# 3923Final.net
KiCad netlist of a schematic drawn in Altium Designer
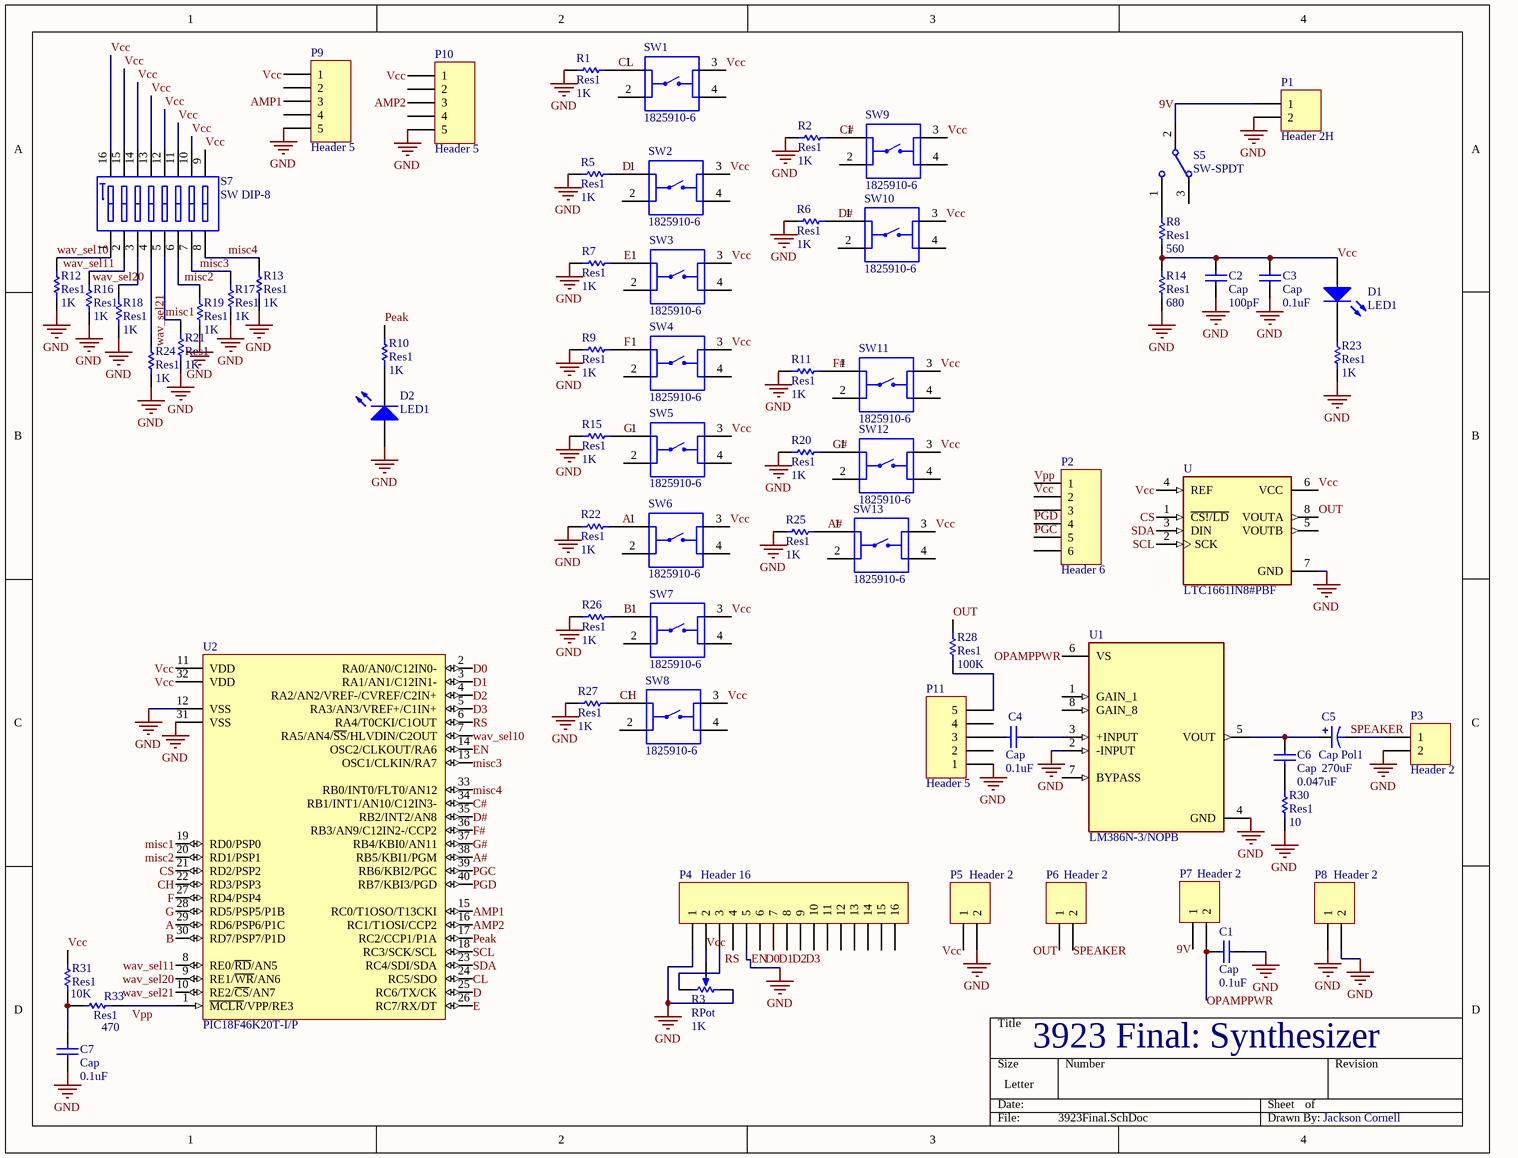
[diagram p0: 3923Final.SchDoc]

(export (version "E")
  (design (tool "Eeschema 10.0.6"))
  (components
    (comp (ref "C1")
      (value "Cap")
      (footprint "RAD-0.3")
      (description "Capacitor")
      (fields (field (name "ALTIUM_VALUE") "0.1uF") (field (name "PUBLISHER") "Altium Limited"))
      (libsource (lib "Miscellaneous Devices") (part "Cap"))
    )
    (comp (ref "C2")
      (value "Cap")
      (footprint "RAD-0.3")
      (description "Capacitor")
      (fields (field (name "ALTIUM_VALUE") "100pF") (field (name "PUBLISHER") "Altium Limited"))
      (libsource (lib "Miscellaneous Devices") (part "Cap"))
    )
    (comp (ref "C3")
      (value "Cap")
      (footprint "RAD-0.3")
      (description "Capacitor")
      (fields (field (name "ALTIUM_VALUE") "0.1uF") (field (name "PUBLISHER") "Altium Limited"))
      (libsource (lib "Miscellaneous Devices") (part "Cap"))
    )
    (comp (ref "C4")
      (value "Cap")
      (footprint "RAD-0.3")
      (description "Capacitor")
      (fields (field (name "ALTIUM_VALUE") "0.1uF") (field (name "PUBLISHER") "Altium Limited"))
      (libsource (lib "Miscellaneous Devices") (part "Cap"))
    )
    (comp (ref "C5")
      (value "Cap Pol1")
      (footprint "RB7.6-15")
      (description "Polarized Capacitor (Radial)")
      (fields (field (name "ALTIUM_VALUE") "270uF") (field (name "PUBLISHER") "Altium Limited"))
      (libsource (lib "Miscellaneous Devices") (part "Cap Pol1"))
    )
    (comp (ref "C6")
      (value "Cap")
      (footprint "RAD-0.3")
      (description "Capacitor")
      (fields (field (name "ALTIUM_VALUE") "0.047uF") (field (name "PUBLISHER") "Altium Limited"))
      (libsource (lib "Miscellaneous Devices") (part "Cap"))
    )
    (comp (ref "C7")
      (value "Cap")
      (footprint "RAD-0.3")
      (description "Capacitor")
      (fields (field (name "ALTIUM_VALUE") "0.1uF") (field (name "PUBLISHER") "Altium Limited"))
      (libsource (lib "Miscellaneous Devices") (part "Cap"))
    )
    (comp (ref "D1")
      (value "LED1")
      (footprint "LED-1")
      (description "Typical RED GaAs LED")
      (fields (field (name "PUBLISHER") "Altium Limited"))
      (libsource (lib "Miscellaneous Devices") (part "LED1"))
    )
    (comp (ref "D2")
      (value "LED1")
      (footprint "LED-1")
      (description "Typical RED GaAs LED")
      (fields (field (name "PUBLISHER") "Altium Limited"))
      (libsource (lib "Miscellaneous Devices") (part "LED1"))
    )
    (comp (ref "P1")
      (value "Header 2H")
      (footprint "HDR1X2H")
      (description "Header, 2-Pin, Right Angle")
      (fields (field (name "PUBLISHER") "Altium Limited"))
      (libsource (lib "Miscellaneous Connectors") (part "Header 2H"))
    )
    (comp (ref "P2")
      (value "Header 6")
      (footprint "HDR1X6")
      (description "Header, 6-Pin")
      (fields (field (name "PUBLISHER") "Altium Limited"))
      (libsource (lib "Miscellaneous Connectors") (part "Header 6"))
    )
    (comp (ref "P3")
      (value "Header 2")
      (footprint "HDR1X2")
      (description "Header, 2-Pin")
      (fields (field (name "PUBLISHER") "Altium Limited"))
      (libsource (lib "") (part "Header 2_1"))
    )
    (comp (ref "P4")
      (value "Header 16")
      (footprint "HDR1X16")
      (description "Header, 16-Pin")
      (fields (field (name "PUBLISHER") "Altium Limited"))
      (libsource (lib "Miscellaneous Connectors") (part "Header 16"))
    )
    (comp (ref "P5")
      (value "Header 2")
      (footprint "HDR1X2")
      (description "Header, 2-Pin")
      (fields (field (name "PUBLISHER") "Altium Limited"))
      (libsource (lib "Miscellaneous Connectors") (part "Header 2"))
    )
    (comp (ref "P6")
      (value "Header 2")
      (footprint "HDR1X2")
      (description "Header, 2-Pin")
      (fields (field (name "PUBLISHER") "Altium Limited"))
      (libsource (lib "Miscellaneous Connectors") (part "Header 2"))
    )
    (comp (ref "P7")
      (value "Header 2")
      (footprint "HDR1X2")
      (description "Header, 2-Pin")
      (fields (field (name "PUBLISHER") "Altium Limited"))
      (libsource (lib "Miscellaneous Connectors") (part "Header 2"))
    )
    (comp (ref "P8")
      (value "Header 2")
      (footprint "HDR1X2")
      (description "Header, 2-Pin")
      (fields (field (name "PUBLISHER") "Altium Limited"))
      (libsource (lib "Miscellaneous Connectors") (part "Header 2"))
    )
    (comp (ref "P9")
      (value "Header 5")
      (footprint "HDR1X5")
      (description "Header, 5-Pin")
      (fields (field (name "PUBLISHER") "Altium Limited"))
      (libsource (lib "") (part "Header 5_1"))
    )
    (comp (ref "P10")
      (value "Header 5")
      (footprint "HDR1X5")
      (description "Header, 5-Pin")
      (fields (field (name "PUBLISHER") "Altium Limited"))
      (libsource (lib "") (part "Header 5_1"))
    )
    (comp (ref "P11")
      (value "Header 5")
      (footprint "HDR1X5")
      (description "Header, 5-Pin")
      (fields (field (name "PUBLISHER") "Altium Limited"))
      (libsource (lib "Miscellaneous Connectors") (part "Header 5"))
    )
    (comp (ref "R1")
      (value "Res1")
      (footprint "AXIAL-0.3")
      (description "Resistor")
      (fields (field (name "ALTIUM_VALUE") "1K") (field (name "PUBLISHER") "Altium Limited"))
      (libsource (lib "Miscellaneous Devices") (part "Res1"))
    )
    (comp (ref "R2")
      (value "Res1")
      (footprint "AXIAL-0.3")
      (description "Resistor")
      (fields (field (name "ALTIUM_VALUE") "1K") (field (name "PUBLISHER") "Altium Limited"))
      (libsource (lib "Miscellaneous Devices") (part "Res1"))
    )
    (comp (ref "R3")
      (value "RPot")
      (footprint "VR5")
      (description "Potentiometer")
      (fields (field (name "ALTIUM_VALUE") "1K") (field (name "PUBLISHER") "Altium Limited"))
      (libsource (lib "Miscellaneous Devices") (part "RPot"))
    )
    (comp (ref "R5")
      (value "Res1")
      (footprint "AXIAL-0.3")
      (description "Resistor")
      (fields (field (name "ALTIUM_VALUE") "1K") (field (name "PUBLISHER") "Altium Limited"))
      (libsource (lib "Miscellaneous Devices") (part "Res1"))
    )
    (comp (ref "R6")
      (value "Res1")
      (footprint "AXIAL-0.3")
      (description "Resistor")
      (fields (field (name "ALTIUM_VALUE") "1K") (field (name "PUBLISHER") "Altium Limited"))
      (libsource (lib "Miscellaneous Devices") (part "Res1"))
    )
    (comp (ref "R7")
      (value "Res1")
      (footprint "AXIAL-0.3")
      (description "Resistor")
      (fields (field (name "ALTIUM_VALUE") "1K") (field (name "PUBLISHER") "Altium Limited"))
      (libsource (lib "Miscellaneous Devices") (part "Res1"))
    )
    (comp (ref "R8")
      (value "Res1")
      (footprint "AXIAL-0.3")
      (description "Resistor")
      (fields (field (name "ALTIUM_VALUE") "560") (field (name "PUBLISHER") "Altium Limited"))
      (libsource (lib "Miscellaneous Devices") (part "Res1"))
    )
    (comp (ref "R9")
      (value "Res1")
      (footprint "AXIAL-0.3")
      (description "Resistor")
      (fields (field (name "ALTIUM_VALUE") "1K") (field (name "PUBLISHER") "Altium Limited"))
      (libsource (lib "Miscellaneous Devices") (part "Res1"))
    )
    (comp (ref "R10")
      (value "Res1")
      (footprint "AXIAL-0.3")
      (description "Resistor")
      (fields (field (name "ALTIUM_VALUE") "1K") (field (name "PUBLISHER") "Altium Limited"))
      (libsource (lib "Miscellaneous Devices") (part "Res1"))
    )
    (comp (ref "R11")
      (value "Res1")
      (footprint "AXIAL-0.3")
      (description "Resistor")
      (fields (field (name "ALTIUM_VALUE") "1K") (field (name "PUBLISHER") "Altium Limited"))
      (libsource (lib "Miscellaneous Devices") (part "Res1"))
    )
    (comp (ref "R12")
      (value "Res1")
      (footprint "AXIAL-0.3")
      (description "Resistor")
      (fields (field (name "ALTIUM_VALUE") "1K") (field (name "PUBLISHER") "Altium Limited"))
      (libsource (lib "Miscellaneous Devices") (part "Res1"))
    )
    (comp (ref "R13")
      (value "Res1")
      (footprint "AXIAL-0.3")
      (description "Resistor")
      (fields (field (name "ALTIUM_VALUE") "1K") (field (name "PUBLISHER") "Altium Limited"))
      (libsource (lib "Miscellaneous Devices") (part "Res1"))
    )
    (comp (ref "R14")
      (value "Res1")
      (footprint "AXIAL-0.3")
      (description "Resistor")
      (fields (field (name "ALTIUM_VALUE") "680") (field (name "PUBLISHER") "Altium Limited"))
      (libsource (lib "Miscellaneous Devices") (part "Res1"))
    )
    (comp (ref "R15")
      (value "Res1")
      (footprint "AXIAL-0.3")
      (description "Resistor")
      (fields (field (name "ALTIUM_VALUE") "1K") (field (name "PUBLISHER") "Altium Limited"))
      (libsource (lib "Miscellaneous Devices") (part "Res1"))
    )
    (comp (ref "R16")
      (value "Res1")
      (footprint "AXIAL-0.3")
      (description "Resistor")
      (fields (field (name "ALTIUM_VALUE") "1K") (field (name "PUBLISHER") "Altium Limited"))
      (libsource (lib "Miscellaneous Devices") (part "Res1"))
    )
    (comp (ref "R17")
      (value "Res1")
      (footprint "AXIAL-0.3")
      (description "Resistor")
      (fields (field (name "ALTIUM_VALUE") "1K") (field (name "PUBLISHER") "Altium Limited"))
      (libsource (lib "Miscellaneous Devices") (part "Res1"))
    )
    (comp (ref "R18")
      (value "Res1")
      (footprint "AXIAL-0.3")
      (description "Resistor")
      (fields (field (name "ALTIUM_VALUE") "1K") (field (name "PUBLISHER") "Altium Limited"))
      (libsource (lib "Miscellaneous Devices") (part "Res1"))
    )
    (comp (ref "R19")
      (value "Res1")
      (footprint "AXIAL-0.3")
      (description "Resistor")
      (fields (field (name "ALTIUM_VALUE") "1K") (field (name "PUBLISHER") "Altium Limited"))
      (libsource (lib "Miscellaneous Devices") (part "Res1"))
    )
    (comp (ref "R20")
      (value "Res1")
      (footprint "AXIAL-0.3")
      (description "Resistor")
      (fields (field (name "ALTIUM_VALUE") "1K") (field (name "PUBLISHER") "Altium Limited"))
      (libsource (lib "Miscellaneous Devices") (part "Res1"))
    )
    (comp (ref "R21")
      (value "Res1")
      (footprint "AXIAL-0.3")
      (description "Resistor")
      (fields (field (name "ALTIUM_VALUE") "1K") (field (name "PUBLISHER") "Altium Limited"))
      (libsource (lib "Miscellaneous Devices") (part "Res1"))
    )
    (comp (ref "R22")
      (value "Res1")
      (footprint "AXIAL-0.3")
      (description "Resistor")
      (fields (field (name "ALTIUM_VALUE") "1K") (field (name "PUBLISHER") "Altium Limited"))
      (libsource (lib "Miscellaneous Devices") (part "Res1"))
    )
    (comp (ref "R23")
      (value "Res1")
      (footprint "AXIAL-0.3")
      (description "Resistor")
      (fields (field (name "ALTIUM_VALUE") "1K") (field (name "PUBLISHER") "Altium Limited"))
      (libsource (lib "Miscellaneous Devices") (part "Res1"))
    )
    (comp (ref "R24")
      (value "Res1")
      (footprint "AXIAL-0.3")
      (description "Resistor")
      (fields (field (name "ALTIUM_VALUE") "1K") (field (name "PUBLISHER") "Altium Limited"))
      (libsource (lib "Miscellaneous Devices") (part "Res1"))
    )
    (comp (ref "R25")
      (value "Res1")
      (footprint "AXIAL-0.3")
      (description "Resistor")
      (fields (field (name "ALTIUM_VALUE") "1K") (field (name "PUBLISHER") "Altium Limited"))
      (libsource (lib "Miscellaneous Devices") (part "Res1"))
    )
    (comp (ref "R26")
      (value "Res1")
      (footprint "AXIAL-0.3")
      (description "Resistor")
      (fields (field (name "ALTIUM_VALUE") "1K") (field (name "PUBLISHER") "Altium Limited"))
      (libsource (lib "Miscellaneous Devices") (part "Res1"))
    )
    (comp (ref "R27")
      (value "Res1")
      (footprint "AXIAL-0.3")
      (description "Resistor")
      (fields (field (name "ALTIUM_VALUE") "1K") (field (name "PUBLISHER") "Altium Limited"))
      (libsource (lib "Miscellaneous Devices") (part "Res1"))
    )
    (comp (ref "R28")
      (value "Res1")
      (footprint "AXIAL-0.3")
      (description "Resistor")
      (fields (field (name "ALTIUM_VALUE") "100K") (field (name "PUBLISHER") "Altium Limited"))
      (libsource (lib "Miscellaneous Devices") (part "Res1"))
    )
    (comp (ref "R30")
      (value "Res1")
      (footprint "AXIAL-0.3")
      (description "Resistor")
      (fields (field (name "ALTIUM_VALUE") "10") (field (name "PUBLISHER") "Altium Limited"))
      (libsource (lib "Miscellaneous Devices") (part "Res1"))
    )
    (comp (ref "R31")
      (value "Res1")
      (footprint "AXIAL-0.3")
      (description "Resistor")
      (fields (field (name "ALTIUM_VALUE") "10K") (field (name "PUBLISHER") "Altium Limited"))
      (libsource (lib "Miscellaneous Devices") (part "Res1"))
    )
    (comp (ref "R33")
      (value "Res1")
      (footprint "AXIAL-0.3")
      (description "Resistor")
      (fields (field (name "ALTIUM_VALUE") "470") (field (name "PUBLISHER") "Altium Limited"))
      (libsource (lib "Miscellaneous Devices") (part "Res1"))
    )
    (comp (ref "S5")
      (value "SW-SPDT")
      (footprint "TL36WW15050")
      (description "SPDT Subminiature Toggle Switch, Right Angle Mounting, Vertical Actuation")
      (fields (field (name "PUBLISHER") "Altium Limited"))
      (libsource (lib "Miscellaneous Devices") (part "SW-SPDT"))
    )
    (comp (ref "S7")
      (value "SW DIP-8")
      (footprint "DIP-16")
      (description "DIP Switch, 8 Position, SPST")
      (fields (field (name "PUBLISHER") "Altium Limited"))
      (libsource (lib "Miscellaneous Devices") (part "SW DIP-8"))
    )
    (comp (ref "SW1")
      (value "1825910-6")
      (footprint "SW_1825910-6-4")
      (description "Switch Push Button OFF _ON_ SPST Round Button 0.05A 24VDC Momentary Contact PC Pins Thru-Hole")
      (fields (field (name "MF") "TE Connectivity") (field (name "DIGI-KEY_PART_NUMBER") "450-1650-ND"))
      (libsource (lib "1825910-6") (part "1825910-6"))
    )
    (comp (ref "SW2")
      (value "1825910-6")
      (footprint "SW_1825910-6-4")
      (description "Switch Push Button OFF _ON_ SPST Round Button 0.05A 24VDC Momentary Contact PC Pins Thru-Hole")
      (fields (field (name "MF") "TE Connectivity") (field (name "DIGI-KEY_PART_NUMBER") "450-1650-ND"))
      (libsource (lib "1825910-6") (part "1825910-6"))
    )
    (comp (ref "SW3")
      (value "1825910-6")
      (footprint "SW_1825910-6-4")
      (description "Switch Push Button OFF _ON_ SPST Round Button 0.05A 24VDC Momentary Contact PC Pins Thru-Hole")
      (fields (field (name "MF") "TE Connectivity") (field (name "DIGI-KEY_PART_NUMBER") "450-1650-ND"))
      (libsource (lib "1825910-6") (part "1825910-6"))
    )
    (comp (ref "SW4")
      (value "1825910-6")
      (footprint "SW_1825910-6-4")
      (description "Switch Push Button OFF _ON_ SPST Round Button 0.05A 24VDC Momentary Contact PC Pins Thru-Hole")
      (fields (field (name "MF") "TE Connectivity") (field (name "DIGI-KEY_PART_NUMBER") "450-1650-ND"))
      (libsource (lib "1825910-6") (part "1825910-6"))
    )
    (comp (ref "SW5")
      (value "1825910-6")
      (footprint "SW_1825910-6-4")
      (description "Switch Push Button OFF _ON_ SPST Round Button 0.05A 24VDC Momentary Contact PC Pins Thru-Hole")
      (fields (field (name "MF") "TE Connectivity") (field (name "DIGI-KEY_PART_NUMBER") "450-1650-ND"))
      (libsource (lib "1825910-6") (part "1825910-6"))
    )
    (comp (ref "SW6")
      (value "1825910-6")
      (footprint "SW_1825910-6-4")
      (description "Switch Push Button OFF _ON_ SPST Round Button 0.05A 24VDC Momentary Contact PC Pins Thru-Hole")
      (fields (field (name "MF") "TE Connectivity") (field (name "DIGI-KEY_PART_NUMBER") "450-1650-ND"))
      (libsource (lib "1825910-6") (part "1825910-6"))
    )
    (comp (ref "SW7")
      (value "1825910-6")
      (footprint "SW_1825910-6-4")
      (description "Switch Push Button OFF _ON_ SPST Round Button 0.05A 24VDC Momentary Contact PC Pins Thru-Hole")
      (fields (field (name "MF") "TE Connectivity") (field (name "DIGI-KEY_PART_NUMBER") "450-1650-ND"))
      (libsource (lib "1825910-6") (part "1825910-6"))
    )
    (comp (ref "SW8")
      (value "1825910-6")
      (footprint "SW_1825910-6-4")
      (description "Switch Push Button OFF _ON_ SPST Round Button 0.05A 24VDC Momentary Contact PC Pins Thru-Hole")
      (fields (field (name "MF") "TE Connectivity") (field (name "DIGI-KEY_PART_NUMBER") "450-1650-ND"))
      (libsource (lib "1825910-6") (part "1825910-6"))
    )
    (comp (ref "SW9")
      (value "1825910-6")
      (footprint "SW_1825910-6-4")
      (description "Switch Push Button OFF _ON_ SPST Round Button 0.05A 24VDC Momentary Contact PC Pins Thru-Hole")
      (fields (field (name "MF") "TE Connectivity") (field (name "DIGI-KEY_PART_NUMBER") "450-1650-ND"))
      (libsource (lib "1825910-6") (part "1825910-6"))
    )
    (comp (ref "SW10")
      (value "1825910-6")
      (footprint "SW_1825910-6-4")
      (description "Switch Push Button OFF _ON_ SPST Round Button 0.05A 24VDC Momentary Contact PC Pins Thru-Hole")
      (fields (field (name "MF") "TE Connectivity") (field (name "DIGI-KEY_PART_NUMBER") "450-1650-ND"))
      (libsource (lib "1825910-6") (part "1825910-6"))
    )
    (comp (ref "SW11")
      (value "1825910-6")
      (footprint "SW_1825910-6-4")
      (description "Switch Push Button OFF _ON_ SPST Round Button 0.05A 24VDC Momentary Contact PC Pins Thru-Hole")
      (fields (field (name "MF") "TE Connectivity") (field (name "DIGI-KEY_PART_NUMBER") "450-1650-ND"))
      (libsource (lib "1825910-6") (part "1825910-6"))
    )
    (comp (ref "SW12")
      (value "1825910-6")
      (footprint "SW_1825910-6-4")
      (description "Switch Push Button OFF _ON_ SPST Round Button 0.05A 24VDC Momentary Contact PC Pins Thru-Hole")
      (fields (field (name "MF") "TE Connectivity") (field (name "DIGI-KEY_PART_NUMBER") "450-1650-ND"))
      (libsource (lib "1825910-6") (part "1825910-6"))
    )
    (comp (ref "SW13")
      (value "1825910-6")
      (footprint "SW_1825910-6-4")
      (description "Switch Push Button OFF _ON_ SPST Round Button 0.05A 24VDC Momentary Contact PC Pins Thru-Hole")
      (fields (field (name "MF") "TE Connectivity") (field (name "DIGI-KEY_PART_NUMBER") "450-1650-ND"))
      (libsource (lib "1825910-6") (part "1825910-6"))
    )
    (comp (ref "U")
      (value "LTC1661IN8#PBF")
      (footprint "DIP794W45P254L959H508Q8")
      (description "10 Bit Digital to Analog Converter 2 8-PDIP")
      (fields (field (name "MF") "Linear Technology/Analog Devices"))
      (libsource (lib "LTC1661IN8_PBF") (part "LTC1661IN8#PBF"))
    )
    (comp (ref "U1")
      (value "LM386N-3/NOPB")
      (footprint "DIP794W45P254L959H508Q8")
      (libsource (lib "LM386N-3_NOPB") (part "LM386N-3/NOPB"))
    )
    (comp (ref "U2")
      (value "PIC18F46K20T-I/P")
      (footprint "PDIP600-P40")
      (libsource (lib "Microchip PIC18") (part "PIC18F46K20T-I/P"))
    )
  )
  (nets
    (net (code "1") (name "/9V") (class "Default")
      (node (ref "P1") (pin "1") (pinfunction "1_1") (pintype "passive"))
      (node (ref "P7") (pin "1") (pinfunction "1_1") (pintype "passive"))
      (node (ref "S5") (pin "2") (pinfunction "2_2") (pintype "passive"))
    )
    (net (code "2") (name "/A") (class "Default")
      (node (ref "R22") (pin "1") (pinfunction "1_1") (pintype "passive"))
      (node (ref "SW6") (pin "1") (pinfunction "1_1") (pintype "passive"))
      (node (ref "U2") (pin "29") (pinfunction "RD6/PSP6/P1C_29") (pintype "bidirectional"))
    )
    (net (code "3") (name "/A#") (class "Default")
      (node (ref "R25") (pin "1") (pinfunction "1_1") (pintype "passive"))
      (node (ref "SW13") (pin "1") (pinfunction "1_1") (pintype "passive"))
      (node (ref "U2") (pin "38") (pinfunction "RB5/KBI1/PGM_38") (pintype "bidirectional"))
    )
    (net (code "4") (name "/AMP1") (class "Default")
      (node (ref "P9") (pin "3") (pinfunction "3_3") (pintype "passive"))
      (node (ref "U2") (pin "15") (pinfunction "RC0/T1OSO/T13CKI_15") (pintype "bidirectional"))
    )
    (net (code "5") (name "/AMP2") (class "Default")
      (node (ref "P10") (pin "3") (pinfunction "3_3") (pintype "passive"))
      (node (ref "U2") (pin "16") (pinfunction "RC1/T1OSI/CCP2_16") (pintype "bidirectional"))
    )
    (net (code "6") (name "/B") (class "Default")
      (node (ref "R26") (pin "1") (pinfunction "1_1") (pintype "passive"))
      (node (ref "SW7") (pin "1") (pinfunction "1_1") (pintype "passive"))
      (node (ref "U2") (pin "30") (pinfunction "RD7/PSP7/P1D_30") (pintype "bidirectional"))
    )
    (net (code "7") (name "/C#") (class "Default")
      (node (ref "R2") (pin "1") (pinfunction "1_1") (pintype "passive"))
      (node (ref "SW9") (pin "1") (pinfunction "1_1") (pintype "passive"))
      (node (ref "U2") (pin "34") (pinfunction "RB1/INT1/AN10/C12IN3-_34") (pintype "bidirectional"))
    )
    (net (code "8") (name "/CH") (class "Default")
      (node (ref "R27") (pin "1") (pinfunction "1_1") (pintype "passive"))
      (node (ref "SW8") (pin "1") (pinfunction "1_1") (pintype "passive"))
      (node (ref "U2") (pin "22") (pinfunction "RD3/PSP3_22") (pintype "bidirectional"))
    )
    (net (code "9") (name "/CL") (class "Default")
      (node (ref "R1") (pin "2") (pinfunction "2_2") (pintype "passive"))
      (node (ref "SW1") (pin "1") (pinfunction "1_1") (pintype "passive"))
      (node (ref "U2") (pin "24") (pinfunction "RC5/SDO_24") (pintype "bidirectional"))
    )
    (net (code "10") (name "/CS") (class "Default")
      (node (ref "U") (pin "1") (pinfunction "~{CS!/LD}_1") (pintype "input"))
      (node (ref "U2") (pin "21") (pinfunction "RD2/PSP2_21") (pintype "bidirectional"))
    )
    (net (code "11") (name "/D") (class "Default")
      (node (ref "R5") (pin "1") (pinfunction "1_1") (pintype "passive"))
      (node (ref "SW2") (pin "1") (pinfunction "1_1") (pintype "passive"))
      (node (ref "U2") (pin "25") (pinfunction "RC6/TX/CK_25") (pintype "bidirectional"))
    )
    (net (code "12") (name "/D#") (class "Default")
      (node (ref "R6") (pin "1") (pinfunction "1_1") (pintype "passive"))
      (node (ref "SW10") (pin "1") (pinfunction "1_1") (pintype "passive"))
      (node (ref "U2") (pin "35") (pinfunction "RB2/INT2/AN8_35") (pintype "bidirectional"))
    )
    (net (code "13") (name "/D0") (class "Default")
      (node (ref "P4") (pin "7") (pinfunction "7_7") (pintype "passive"))
      (node (ref "U2") (pin "2") (pinfunction "RA0/AN0/C12IN0-_2") (pintype "bidirectional"))
    )
    (net (code "14") (name "/D1") (class "Default")
      (node (ref "P4") (pin "8") (pinfunction "8_8") (pintype "passive"))
      (node (ref "U2") (pin "3") (pinfunction "RA1/AN1/C12IN1-_3") (pintype "bidirectional"))
    )
    (net (code "15") (name "/D2") (class "Default")
      (node (ref "P4") (pin "9") (pinfunction "9_9") (pintype "passive"))
      (node (ref "U2") (pin "4") (pinfunction "RA2/AN2/VREF-/CVREF/C2IN+_4") (pintype "bidirectional"))
    )
    (net (code "16") (name "/D3") (class "Default")
      (node (ref "P4") (pin "10") (pinfunction "10_10") (pintype "passive"))
      (node (ref "U2") (pin "5") (pinfunction "RA3/AN3/VREF+/C1IN+_5") (pintype "bidirectional"))
    )
    (net (code "17") (name "/E") (class "Default")
      (node (ref "R7") (pin "1") (pinfunction "1_1") (pintype "passive"))
      (node (ref "SW3") (pin "1") (pinfunction "1_1") (pintype "passive"))
      (node (ref "U2") (pin "26") (pinfunction "RC7/RX/DT_26") (pintype "bidirectional"))
    )
    (net (code "18") (name "/EN") (class "Default")
      (node (ref "P4") (pin "6") (pinfunction "6_6") (pintype "passive"))
      (node (ref "U2") (pin "14") (pinfunction "OSC2/CLKOUT/RA6_14") (pintype "bidirectional"))
    )
    (net (code "19") (name "/F") (class "Default")
      (node (ref "R9") (pin "1") (pinfunction "1_1") (pintype "passive"))
      (node (ref "SW4") (pin "1") (pinfunction "1_1") (pintype "passive"))
      (node (ref "U2") (pin "27") (pinfunction "RD4/PSP4_27") (pintype "bidirectional"))
    )
    (net (code "20") (name "/F#") (class "Default")
      (node (ref "R11") (pin "1") (pinfunction "1_1") (pintype "passive"))
      (node (ref "SW11") (pin "1") (pinfunction "1_1") (pintype "passive"))
      (node (ref "U2") (pin "36") (pinfunction "RB3/AN9/C12IN2-/CCP2_36") (pintype "bidirectional"))
    )
    (net (code "21") (name "/G") (class "Default")
      (node (ref "R15") (pin "1") (pinfunction "1_1") (pintype "passive"))
      (node (ref "SW5") (pin "1") (pinfunction "1_1") (pintype "passive"))
      (node (ref "U2") (pin "28") (pinfunction "RD5/PSP5/P1B_28") (pintype "bidirectional"))
    )
    (net (code "22") (name "/G#") (class "Default")
      (node (ref "R20") (pin "1") (pinfunction "1_1") (pintype "passive"))
      (node (ref "SW12") (pin "1") (pinfunction "1_1") (pintype "passive"))
      (node (ref "U2") (pin "37") (pinfunction "RB4/KBI0/AN11_37") (pintype "bidirectional"))
    )
    (net (code "23") (name "/OPAMPPWR") (class "Default")
      (node (ref "C1") (pin "2") (pinfunction "2_2") (pintype "passive"))
      (node (ref "P7") (pin "2") (pinfunction "2_2") (pintype "passive"))
      (node (ref "U1") (pin "6") (pinfunction "VS_6") (pintype "power_in"))
    )
    (net (code "24") (name "/OUT") (class "Default")
      (node (ref "P6") (pin "1") (pinfunction "1_1") (pintype "passive"))
      (node (ref "R28") (pin "2") (pinfunction "2_2") (pintype "passive"))
      (node (ref "U") (pin "8") (pinfunction "VOUTA_8") (pintype "output"))
    )
    (net (code "25") (name "/PGC") (class "Default")
      (node (ref "P2") (pin "5") (pinfunction "5_5") (pintype "passive"))
      (node (ref "U2") (pin "39") (pinfunction "RB6/KBI2/PGC_39") (pintype "bidirectional"))
    )
    (net (code "26") (name "/PGD") (class "Default")
      (node (ref "P2") (pin "4") (pinfunction "4_4") (pintype "passive"))
      (node (ref "U2") (pin "40") (pinfunction "RB7/KBI3/PGD_40") (pintype "bidirectional"))
    )
    (net (code "27") (name "/Peak") (class "Default")
      (node (ref "R10") (pin "1") (pinfunction "1_1") (pintype "passive"))
      (node (ref "U2") (pin "17") (pinfunction "RC2/CCP1/P1A_17") (pintype "bidirectional"))
    )
    (net (code "28") (name "/RS") (class "Default")
      (node (ref "P4") (pin "4") (pinfunction "4_4") (pintype "passive"))
      (node (ref "U2") (pin "6") (pinfunction "RA4/T0CKI/C1OUT_6") (pintype "bidirectional"))
    )
    (net (code "29") (name "/SCL") (class "Default")
      (node (ref "U") (pin "2") (pinfunction "SCK_2") (pintype "input"))
      (node (ref "U2") (pin "18") (pinfunction "RC3/SCK/SCL_18") (pintype "bidirectional"))
    )
    (net (code "30") (name "/SDA") (class "Default")
      (node (ref "U") (pin "3") (pinfunction "DIN_3") (pintype "input"))
      (node (ref "U2") (pin "23") (pinfunction "RC4/SDI/SDA_23") (pintype "bidirectional"))
    )
    (net (code "31") (name "/SPEAKER") (class "Default")
      (node (ref "C5") (pin "2") (pinfunction "2_2") (pintype "passive"))
      (node (ref "P3") (pin "1") (pinfunction "1_1") (pintype "passive"))
      (node (ref "P6") (pin "2") (pinfunction "2_2") (pintype "passive"))
    )
    (net (code "32") (name "/Vcc") (class "Default")
      (node (ref "C2") (pin "2") (pinfunction "2_2") (pintype "passive"))
      (node (ref "C3") (pin "2") (pinfunction "2_2") (pintype "passive"))
      (node (ref "D1") (pin "1") (pinfunction "A_1") (pintype "passive"))
      (node (ref "P10") (pin "1") (pinfunction "1_1") (pintype "passive"))
      (node (ref "P2") (pin "2") (pinfunction "2_2") (pintype "passive"))
      (node (ref "P4") (pin "2") (pinfunction "2_2") (pintype "passive"))
      (node (ref "P5") (pin "1") (pinfunction "1_1") (pintype "passive"))
      (node (ref "P9") (pin "1") (pinfunction "1_1") (pintype "passive"))
      (node (ref "R14") (pin "2") (pinfunction "2_2") (pintype "passive"))
      (node (ref "R3") (pin "3") (pinfunction "TAP_3") (pintype "passive"))
      (node (ref "R31") (pin "2") (pinfunction "2_2") (pintype "passive"))
      (node (ref "R8") (pin "1") (pinfunction "1_1") (pintype "passive"))
      (node (ref "S7") (pin "10") (pinfunction "B7_10") (pintype "passive"))
      (node (ref "S7") (pin "11") (pinfunction "B6_11") (pintype "passive"))
      (node (ref "S7") (pin "12") (pinfunction "B5_12") (pintype "passive"))
      (node (ref "S7") (pin "13") (pinfunction "B4_13") (pintype "passive"))
      (node (ref "S7") (pin "14") (pinfunction "B3_14") (pintype "passive"))
      (node (ref "S7") (pin "15") (pinfunction "B2_15") (pintype "passive"))
      (node (ref "S7") (pin "16") (pinfunction "B1_16") (pintype "passive"))
      (node (ref "S7") (pin "9") (pinfunction "B8_9") (pintype "passive"))
      (node (ref "SW1") (pin "3") (pinfunction "3_3") (pintype "passive"))
      (node (ref "SW10") (pin "3") (pinfunction "3_3") (pintype "passive"))
      (node (ref "SW11") (pin "3") (pinfunction "3_3") (pintype "passive"))
      (node (ref "SW12") (pin "3") (pinfunction "3_3") (pintype "passive"))
      (node (ref "SW13") (pin "3") (pinfunction "3_3") (pintype "passive"))
      (node (ref "SW2") (pin "3") (pinfunction "3_3") (pintype "passive"))
      (node (ref "SW3") (pin "3") (pinfunction "3_3") (pintype "passive"))
      (node (ref "SW4") (pin "3") (pinfunction "3_3") (pintype "passive"))
      (node (ref "SW5") (pin "3") (pinfunction "3_3") (pintype "passive"))
      (node (ref "SW6") (pin "3") (pinfunction "3_3") (pintype "passive"))
      (node (ref "SW7") (pin "3") (pinfunction "3_3") (pintype "passive"))
      (node (ref "SW8") (pin "3") (pinfunction "3_3") (pintype "passive"))
      (node (ref "SW9") (pin "3") (pinfunction "3_3") (pintype "passive"))
      (node (ref "U") (pin "4") (pinfunction "REF_4") (pintype "input"))
      (node (ref "U") (pin "6") (pinfunction "VCC_6") (pintype "power_in"))
      (node (ref "U2") (pin "11") (pinfunction "VDD_11") (pintype "power_in"))
      (node (ref "U2") (pin "32") (pinfunction "VDD_32") (pintype "power_in"))
    )
    (net (code "33") (name "/Vpp") (class "Default")
      (node (ref "P2") (pin "1") (pinfunction "1_1") (pintype "passive"))
      (node (ref "R33") (pin "1") (pinfunction "1_1") (pintype "passive"))
      (node (ref "U2") (pin "1") (pinfunction "~{MCLR}/VPP/RE3_1") (pintype "input"))
    )
    (net (code "34") (name "/misc1") (class "Default")
      (node (ref "R21") (pin "1") (pinfunction "1_1") (pintype "passive"))
      (node (ref "S7") (pin "5") (pinfunction "A5_5") (pintype "passive"))
      (node (ref "U2") (pin "19") (pinfunction "RD0/PSP0_19") (pintype "bidirectional"))
    )
    (net (code "35") (name "/misc2") (class "Default")
      (node (ref "R19") (pin "1") (pinfunction "1_1") (pintype "passive"))
      (node (ref "S7") (pin "6") (pinfunction "A6_6") (pintype "passive"))
      (node (ref "U2") (pin "20") (pinfunction "RD1/PSP1_20") (pintype "bidirectional"))
    )
    (net (code "36") (name "/misc3") (class "Default")
      (node (ref "R17") (pin "1") (pinfunction "1_1") (pintype "passive"))
      (node (ref "S7") (pin "7") (pinfunction "A7_7") (pintype "passive"))
      (node (ref "U2") (pin "13") (pinfunction "OSC1/CLKIN/RA7_13") (pintype "bidirectional"))
    )
    (net (code "37") (name "/misc4") (class "Default")
      (node (ref "R13") (pin "1") (pinfunction "1_1") (pintype "passive"))
      (node (ref "S7") (pin "8") (pinfunction "A8_8") (pintype "passive"))
      (node (ref "U2") (pin "33") (pinfunction "RB0/INT0/FLT0/AN12_33") (pintype "bidirectional"))
    )
    (net (code "38") (name "/wav_sel10") (class "Default")
      (node (ref "R12") (pin "2") (pinfunction "2_2") (pintype "passive"))
      (node (ref "S7") (pin "1") (pinfunction "A1_1") (pintype "passive"))
      (node (ref "U2") (pin "7") (pinfunction "RA5/AN4/~{SS}/HLVDIN/C2OUT_7") (pintype "bidirectional"))
    )
    (net (code "39") (name "/wav_sel11") (class "Default")
      (node (ref "R16") (pin "2") (pinfunction "2_2") (pintype "passive"))
      (node (ref "S7") (pin "2") (pinfunction "A2_2") (pintype "passive"))
      (node (ref "U2") (pin "8") (pinfunction "RE0/~{RD}/AN5_8") (pintype "bidirectional"))
    )
    (net (code "40") (name "/wav_sel20") (class "Default")
      (node (ref "R18") (pin "1") (pinfunction "1_1") (pintype "passive"))
      (node (ref "S7") (pin "3") (pinfunction "A3_3") (pintype "passive"))
      (node (ref "U2") (pin "9") (pinfunction "RE1/~{WR}/AN6_9") (pintype "bidirectional"))
    )
    (net (code "41") (name "/wav_sel21") (class "Default")
      (node (ref "R24") (pin "1") (pinfunction "1_1") (pintype "passive"))
      (node (ref "S7") (pin "4") (pinfunction "A4_4") (pintype "passive"))
      (node (ref "U2") (pin "10") (pinfunction "RE2/~{CS}/AN7_10") (pintype "bidirectional"))
    )
    (net (code "42") (name "GND") (class "Default")
      (node (ref "C1") (pin "1") (pinfunction "1_1") (pintype "passive"))
      (node (ref "C2") (pin "1") (pinfunction "1_1") (pintype "passive"))
      (node (ref "C3") (pin "1") (pinfunction "1_1") (pintype "passive"))
      (node (ref "C7") (pin "1") (pinfunction "1_1") (pintype "passive"))
      (node (ref "D2") (pin "1") (pinfunction "A_1") (pintype "passive"))
      (node (ref "P1") (pin "2") (pinfunction "2_2") (pintype "passive"))
      (node (ref "P10") (pin "5") (pinfunction "5_5") (pintype "passive"))
      (node (ref "P11") (pin "1") (pinfunction "1_1") (pintype "passive"))
      (node (ref "P3") (pin "2") (pinfunction "2_2") (pintype "passive"))
      (node (ref "P4") (pin "1") (pinfunction "1_1") (pintype "passive"))
      (node (ref "P4") (pin "5") (pinfunction "5_5") (pintype "passive"))
      (node (ref "P5") (pin "2") (pinfunction "2_2") (pintype "passive"))
      (node (ref "P8") (pin "1") (pinfunction "1_1") (pintype "passive"))
      (node (ref "P8") (pin "2") (pinfunction "2_2") (pintype "passive"))
      (node (ref "P9") (pin "5") (pinfunction "5_5") (pintype "passive"))
      (node (ref "R1") (pin "1") (pinfunction "1_1") (pintype "passive"))
      (node (ref "R11") (pin "2") (pinfunction "2_2") (pintype "passive"))
      (node (ref "R12") (pin "1") (pinfunction "1_1") (pintype "passive"))
      (node (ref "R13") (pin "2") (pinfunction "2_2") (pintype "passive"))
      (node (ref "R14") (pin "1") (pinfunction "1_1") (pintype "passive"))
      (node (ref "R15") (pin "2") (pinfunction "2_2") (pintype "passive"))
      (node (ref "R16") (pin "1") (pinfunction "1_1") (pintype "passive"))
      (node (ref "R17") (pin "2") (pinfunction "2_2") (pintype "passive"))
      (node (ref "R18") (pin "2") (pinfunction "2_2") (pintype "passive"))
      (node (ref "R19") (pin "2") (pinfunction "2_2") (pintype "passive"))
      (node (ref "R2") (pin "2") (pinfunction "2_2") (pintype "passive"))
      (node (ref "R20") (pin "2") (pinfunction "2_2") (pintype "passive"))
      (node (ref "R21") (pin "2") (pinfunction "2_2") (pintype "passive"))
      (node (ref "R22") (pin "2") (pinfunction "2_2") (pintype "passive"))
      (node (ref "R23") (pin "2") (pinfunction "2_2") (pintype "passive"))
      (node (ref "R24") (pin "2") (pinfunction "2_2") (pintype "passive"))
      (node (ref "R25") (pin "2") (pinfunction "2_2") (pintype "passive"))
      (node (ref "R26") (pin "2") (pinfunction "2_2") (pintype "passive"))
      (node (ref "R27") (pin "2") (pinfunction "2_2") (pintype "passive"))
      (node (ref "R3") (pin "1") (pinfunction "TOP_1") (pintype "passive"))
      (node (ref "R30") (pin "2") (pinfunction "2_2") (pintype "passive"))
      (node (ref "R5") (pin "2") (pinfunction "2_2") (pintype "passive"))
      (node (ref "R6") (pin "2") (pinfunction "2_2") (pintype "passive"))
      (node (ref "R7") (pin "2") (pinfunction "2_2") (pintype "passive"))
      (node (ref "R9") (pin "2") (pinfunction "2_2") (pintype "passive"))
      (node (ref "U") (pin "7") (pinfunction "GND_7") (pintype "power_in"))
      (node (ref "U1") (pin "2") (pinfunction "-INPUT_2") (pintype "input"))
      (node (ref "U1") (pin "4") (pinfunction "GND_4") (pintype "power_in"))
      (node (ref "U2") (pin "12") (pinfunction "VSS_12") (pintype "power_in"))
      (node (ref "U2") (pin "31") (pinfunction "VSS_31") (pintype "power_in"))
    )
    (net (code "43") (name "Net-(C4-Pad1)") (class "Default")
      (node (ref "C4") (pin "1") (pinfunction "1_1") (pintype "passive"))
      (node (ref "P11") (pin "3") (pinfunction "3_3") (pintype "passive"))
    )
    (net (code "44") (name "Net-(C6-Pad1)") (class "Default")
      (node (ref "C6") (pin "1") (pinfunction "1_1") (pintype "passive"))
      (node (ref "R30") (pin "1") (pinfunction "1_1") (pintype "passive"))
    )
    (net (code "45") (name "Net-(C7-Pad2)") (class "Default")
      (node (ref "C7") (pin "2") (pinfunction "2_2") (pintype "passive"))
      (node (ref "R31") (pin "1") (pinfunction "1_1") (pintype "passive"))
      (node (ref "R33") (pin "2") (pinfunction "2_2") (pintype "passive"))
    )
    (net (code "46") (name "Net-(D1-K)") (class "Default")
      (node (ref "D1") (pin "2") (pinfunction "K_2") (pintype "passive"))
      (node (ref "R23") (pin "1") (pinfunction "1_1") (pintype "passive"))
    )
    (net (code "47") (name "Net-(D2-K)") (class "Default")
      (node (ref "D2") (pin "2") (pinfunction "K_2") (pintype "passive"))
      (node (ref "R10") (pin "2") (pinfunction "2_2") (pintype "passive"))
    )
    (net (code "48") (name "Net-(P11-Pad5)") (class "Default")
      (node (ref "P11") (pin "5") (pinfunction "5_5") (pintype "passive"))
      (node (ref "R28") (pin "1") (pinfunction "1_1") (pintype "passive"))
    )
    (net (code "49") (name "Net-(R3-BOT)") (class "Default")
      (node (ref "P4") (pin "3") (pinfunction "3_3") (pintype "passive"))
      (node (ref "R3") (pin "2") (pinfunction "BOT_2") (pintype "passive"))
    )
    (net (code "50") (name "Net-(R8-Pad2)") (class "Default")
      (node (ref "R8") (pin "2") (pinfunction "2_2") (pintype "passive"))
      (node (ref "S5") (pin "1") (pinfunction "1_1") (pintype "passive"))
    )
    (net (code "51") (name "Net-(U1-+INPUT)") (class "Default")
      (node (ref "C4") (pin "2") (pinfunction "2_2") (pintype "passive"))
      (node (ref "U1") (pin "3") (pinfunction "+INPUT_3") (pintype "input"))
    )
    (net (code "52") (name "Net-(U1-VOUT)") (class "Default")
      (node (ref "C5") (pin "1") (pinfunction "1_1") (pintype "passive"))
      (node (ref "C6") (pin "2") (pinfunction "2_2") (pintype "passive"))
      (node (ref "U1") (pin "5") (pinfunction "VOUT_5") (pintype "output"))
    )
    (net (code "53") (name "unconnected-(P2-Pad3)") (class "Default")
      (node (ref "P2") (pin "3") (pinfunction "3_3") (pintype "passive"))
    )
    (net (code "54") (name "unconnected-(P2-Pad6)") (class "Default")
      (node (ref "P2") (pin "6") (pinfunction "6_6") (pintype "passive"))
    )
    (net (code "55") (name "unconnected-(P4-Pad11)") (class "Default")
      (node (ref "P4") (pin "11") (pinfunction "11_11") (pintype "passive"))
    )
    (net (code "56") (name "unconnected-(P4-Pad12)") (class "Default")
      (node (ref "P4") (pin "12") (pinfunction "12_12") (pintype "passive"))
    )
    (net (code "57") (name "unconnected-(P4-Pad13)") (class "Default")
      (node (ref "P4") (pin "13") (pinfunction "13_13") (pintype "passive"))
    )
    (net (code "58") (name "unconnected-(P4-Pad14)") (class "Default")
      (node (ref "P4") (pin "14") (pinfunction "14_14") (pintype "passive"))
    )
    (net (code "59") (name "unconnected-(P4-Pad15)") (class "Default")
      (node (ref "P4") (pin "15") (pinfunction "15_15") (pintype "passive"))
    )
    (net (code "60") (name "unconnected-(P4-Pad16)") (class "Default")
      (node (ref "P4") (pin "16") (pinfunction "16_16") (pintype "passive"))
    )
    (net (code "61") (name "unconnected-(P9-Pad2)") (class "Default")
      (node (ref "P9") (pin "2") (pinfunction "2_2") (pintype "passive"))
    )
    (net (code "62") (name "unconnected-(P9-Pad4)") (class "Default")
      (node (ref "P9") (pin "4") (pinfunction "4_4") (pintype "passive"))
    )
    (net (code "63") (name "unconnected-(P10-Pad2)") (class "Default")
      (node (ref "P10") (pin "2") (pinfunction "2_2") (pintype "passive"))
    )
    (net (code "64") (name "unconnected-(P10-Pad4)") (class "Default")
      (node (ref "P10") (pin "4") (pinfunction "4_4") (pintype "passive"))
    )
    (net (code "65") (name "unconnected-(P11-Pad2)") (class "Default")
      (node (ref "P11") (pin "2") (pinfunction "2_2") (pintype "passive"))
    )
    (net (code "66") (name "unconnected-(P11-Pad4)") (class "Default")
      (node (ref "P11") (pin "4") (pinfunction "4_4") (pintype "passive"))
    )
    (net (code "67") (name "unconnected-(S5-Pad3)") (class "Default")
      (node (ref "S5") (pin "3") (pinfunction "3_3") (pintype "passive"))
    )
    (net (code "68") (name "unconnected-(SW1-Pad2)") (class "Default")
      (node (ref "SW1") (pin "2") (pinfunction "2_2") (pintype "passive"))
    )
    (net (code "69") (name "unconnected-(SW1-Pad4)") (class "Default")
      (node (ref "SW1") (pin "4") (pinfunction "4_4") (pintype "passive"))
    )
    (net (code "70") (name "unconnected-(SW2-Pad2)") (class "Default")
      (node (ref "SW2") (pin "2") (pinfunction "2_2") (pintype "passive"))
    )
    (net (code "71") (name "unconnected-(SW2-Pad4)") (class "Default")
      (node (ref "SW2") (pin "4") (pinfunction "4_4") (pintype "passive"))
    )
    (net (code "72") (name "unconnected-(SW3-Pad2)") (class "Default")
      (node (ref "SW3") (pin "2") (pinfunction "2_2") (pintype "passive"))
    )
    (net (code "73") (name "unconnected-(SW3-Pad4)") (class "Default")
      (node (ref "SW3") (pin "4") (pinfunction "4_4") (pintype "passive"))
    )
    (net (code "74") (name "unconnected-(SW4-Pad2)") (class "Default")
      (node (ref "SW4") (pin "2") (pinfunction "2_2") (pintype "passive"))
    )
    (net (code "75") (name "unconnected-(SW4-Pad4)") (class "Default")
      (node (ref "SW4") (pin "4") (pinfunction "4_4") (pintype "passive"))
    )
    (net (code "76") (name "unconnected-(SW5-Pad2)") (class "Default")
      (node (ref "SW5") (pin "2") (pinfunction "2_2") (pintype "passive"))
    )
    (net (code "77") (name "unconnected-(SW5-Pad4)") (class "Default")
      (node (ref "SW5") (pin "4") (pinfunction "4_4") (pintype "passive"))
    )
    (net (code "78") (name "unconnected-(SW6-Pad2)") (class "Default")
      (node (ref "SW6") (pin "2") (pinfunction "2_2") (pintype "passive"))
    )
    (net (code "79") (name "unconnected-(SW6-Pad4)") (class "Default")
      (node (ref "SW6") (pin "4") (pinfunction "4_4") (pintype "passive"))
    )
    (net (code "80") (name "unconnected-(SW7-Pad2)") (class "Default")
      (node (ref "SW7") (pin "2") (pinfunction "2_2") (pintype "passive"))
    )
    (net (code "81") (name "unconnected-(SW7-Pad4)") (class "Default")
      (node (ref "SW7") (pin "4") (pinfunction "4_4") (pintype "passive"))
    )
    (net (code "82") (name "unconnected-(SW8-Pad2)") (class "Default")
      (node (ref "SW8") (pin "2") (pinfunction "2_2") (pintype "passive"))
    )
    (net (code "83") (name "unconnected-(SW8-Pad4)") (class "Default")
      (node (ref "SW8") (pin "4") (pinfunction "4_4") (pintype "passive"))
    )
    (net (code "84") (name "unconnected-(SW9-Pad2)") (class "Default")
      (node (ref "SW9") (pin "2") (pinfunction "2_2") (pintype "passive"))
    )
    (net (code "85") (name "unconnected-(SW9-Pad4)") (class "Default")
      (node (ref "SW9") (pin "4") (pinfunction "4_4") (pintype "passive"))
    )
    (net (code "86") (name "unconnected-(SW10-Pad2)") (class "Default")
      (node (ref "SW10") (pin "2") (pinfunction "2_2") (pintype "passive"))
    )
    (net (code "87") (name "unconnected-(SW10-Pad4)") (class "Default")
      (node (ref "SW10") (pin "4") (pinfunction "4_4") (pintype "passive"))
    )
    (net (code "88") (name "unconnected-(SW11-Pad2)") (class "Default")
      (node (ref "SW11") (pin "2") (pinfunction "2_2") (pintype "passive"))
    )
    (net (code "89") (name "unconnected-(SW11-Pad4)") (class "Default")
      (node (ref "SW11") (pin "4") (pinfunction "4_4") (pintype "passive"))
    )
    (net (code "90") (name "unconnected-(SW12-Pad2)") (class "Default")
      (node (ref "SW12") (pin "2") (pinfunction "2_2") (pintype "passive"))
    )
    (net (code "91") (name "unconnected-(SW12-Pad4)") (class "Default")
      (node (ref "SW12") (pin "4") (pinfunction "4_4") (pintype "passive"))
    )
    (net (code "92") (name "unconnected-(SW13-Pad2)") (class "Default")
      (node (ref "SW13") (pin "2") (pinfunction "2_2") (pintype "passive"))
    )
    (net (code "93") (name "unconnected-(SW13-Pad4)") (class "Default")
      (node (ref "SW13") (pin "4") (pinfunction "4_4") (pintype "passive"))
    )
    (net (code "94") (name "unconnected-(U-VOUTB-Pad5)") (class "Default")
      (node (ref "U") (pin "5") (pinfunction "VOUTB_5") (pintype "output"))
    )
    (net (code "95") (name "unconnected-(U1-BYPASS-Pad7)") (class "Default")
      (node (ref "U1") (pin "7") (pinfunction "BYPASS_7") (pintype "input"))
    )
    (net (code "96") (name "unconnected-(U1-GAIN_1-Pad1)") (class "Default")
      (node (ref "U1") (pin "1") (pinfunction "GAIN_1_1") (pintype "input"))
    )
    (net (code "97") (name "unconnected-(U1-GAIN_8-Pad8)") (class "Default")
      (node (ref "U1") (pin "8") (pinfunction "GAIN_8_8") (pintype "input"))
    )
  )
)
